# pca63100_current_measurement.net
KiCad netlist of a schematic drawn in Altium Designer
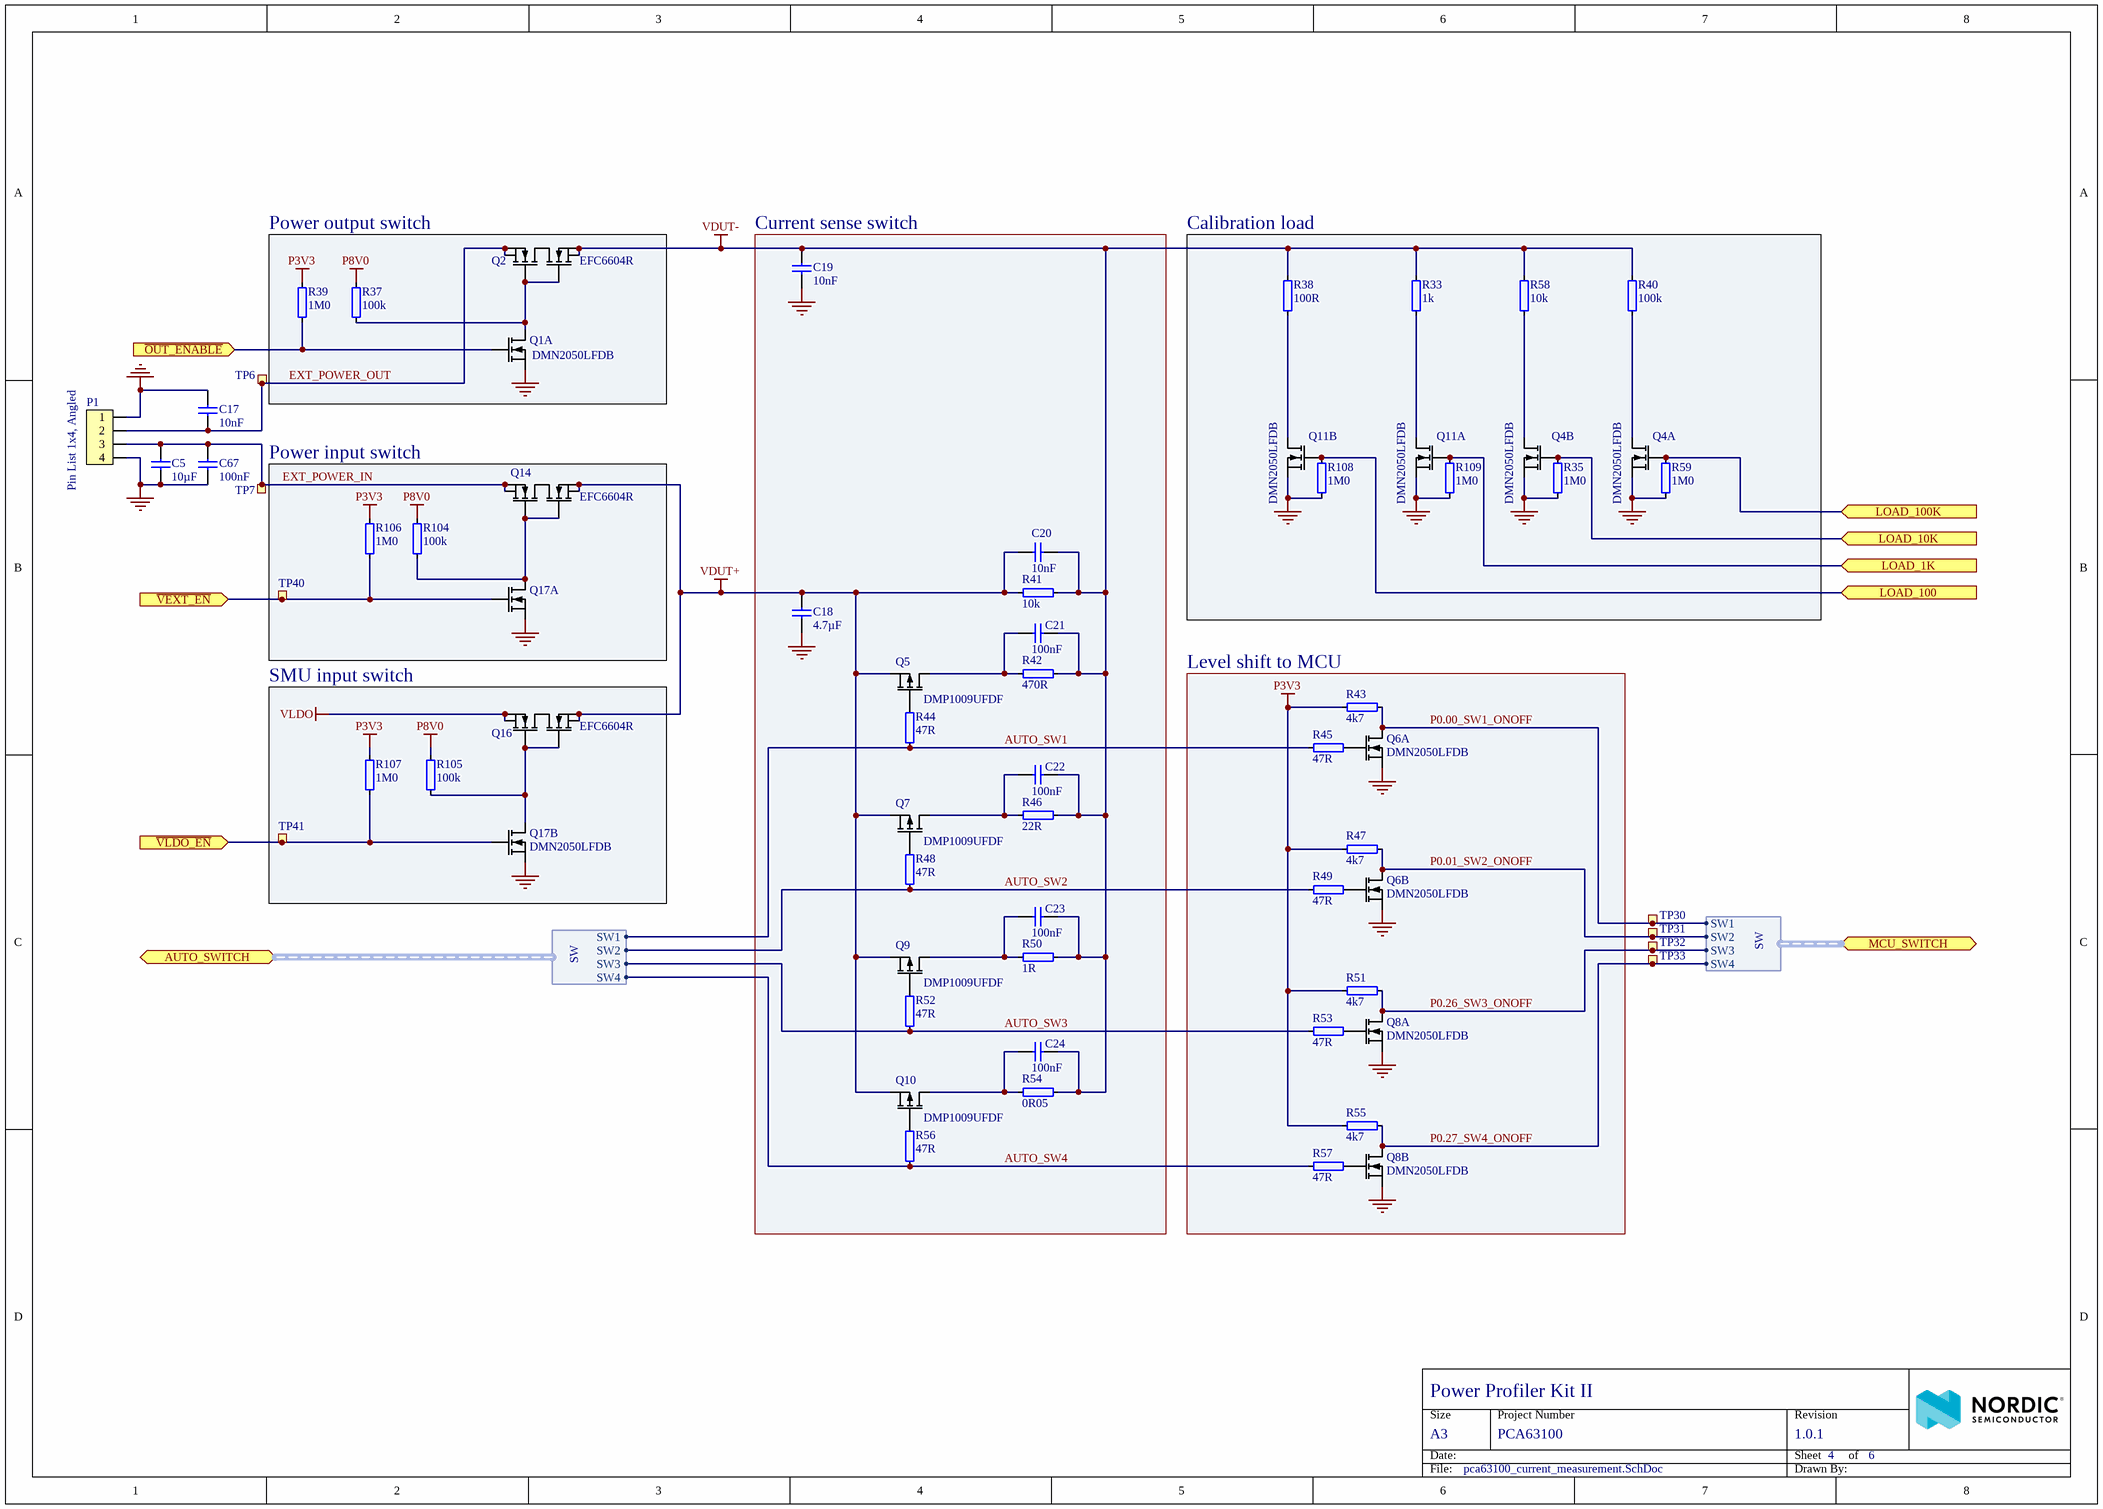
[diagram p0: pca63100_current_measurement.SchDoc]

(export (version "E")
  (design (tool "Eeschema 10.0.6"))
  (components
    (comp (ref "C5")
      (value "10µF")
      (footprint "CAPC1608X06L")
      (description "CAP CER 10UF 10V X7T 0603")
      (fields
        (field (name "PART NUMBER") "0603-10u-10V-X7T-GRM188")
        (field (name "MANUFACTURER") "Murata")
        (field (name "PUBLISHER") "Nordic Semiconductor")
      )
      (libsource (lib "AltiumLib") (part "CAP"))
    )
    (comp (ref "C17")
      (value "10nF")
      (footprint "CAPC0603X03L_C")
      (description "Capacitor, X7R, ±10%")
      (fields (field (name "PART NUMBER") "C0201-10n") (field (name "PUBLISHER") "Nordic Semiconductor"))
      (libsource (lib "AltiumLib") (part "CAP"))
    )
    (comp (ref "C18")
      (value "4.7µF")
      (footprint "CAPC1005X04L")
      (description "Capacitor, X5R, ±20%")
      (fields (field (name "PART NUMBER") "C0402-4µ7") (field (name "PUBLISHER") "Nordic Semiconductor"))
      (libsource (lib "AltiumLib") (part "CAP"))
    )
    (comp (ref "C19")
      (value "10nF")
      (footprint "CAPC0603X03L_C")
      (description "Capacitor, X7R, ±10%")
      (fields (field (name "PART NUMBER") "C0201-10n") (field (name "PUBLISHER") "Nordic Semiconductor"))
      (libsource (lib "AltiumLib") (part "CAP"))
    )
    (comp (ref "C20")
      (value "10nF")
      (footprint "CAPC0603X03L_C")
      (description "Capacitor, X7R, ±10%")
      (fields (field (name "PART NUMBER") "C0201-10n") (field (name "PUBLISHER") "Nordic Semiconductor"))
      (libsource (lib "AltiumLib") (part "CAP"))
    )
    (comp (ref "C21")
      (value "100nF")
      (footprint "CAPC0603X03L_C")
      (description "Capacitor, X5R, ±10%")
      (fields (field (name "PART NUMBER") "C0201-100n") (field (name "PUBLISHER") "Nordic Semiconductor"))
      (libsource (lib "AltiumLib") (part "CAP"))
    )
    (comp (ref "C22")
      (value "100nF")
      (footprint "CAPC0603X03L_C")
      (description "Capacitor, X5R, ±10%")
      (fields (field (name "PART NUMBER") "C0201-100n") (field (name "PUBLISHER") "Nordic Semiconductor"))
      (libsource (lib "AltiumLib") (part "CAP"))
    )
    (comp (ref "C23")
      (value "100nF")
      (footprint "CAPC0603X03L_C")
      (description "Capacitor, X5R, ±10%")
      (fields (field (name "PART NUMBER") "C0201-100n") (field (name "PUBLISHER") "Nordic Semiconductor"))
      (libsource (lib "AltiumLib") (part "CAP"))
    )
    (comp (ref "C24")
      (value "100nF")
      (footprint "CAPC0603X03L_C")
      (description "Capacitor, X5R, ±10%")
      (fields (field (name "PART NUMBER") "C0201-100n") (field (name "PUBLISHER") "Nordic Semiconductor"))
      (libsource (lib "AltiumLib") (part "CAP"))
    )
    (comp (ref "C67")
      (value "100nF")
      (footprint "CAPC0603X03L_C")
      (description "Capacitor, X5R, ±10%")
      (fields (field (name "PART NUMBER") "C0201-100n") (field (name "PUBLISHER") "Nordic Semiconductor"))
      (libsource (lib "AltiumLib") (part "CAP"))
    )
    (comp (ref "P1")
      (value "Pin List 1x4, Angled")
      (footprint "LIST_ANG_1x4-SMD-2.54MM")
      (description "Pin List 1x4, 2.54mm (100mil), Right Angled, SMD")
      (fields
        (field (name "PART NUMBER") "Pin List Ang 1x4 SMD, 2.54mm")
        (field (name "PUBLISHER") "Nordic Semiconductor")
      )
      (libsource (lib "AltiumLib") (part "CONN-4"))
    )
    (comp (ref "Q1")
      (value "DMN2050LFDB")
      (footprint "DFN65P200X60_HS-6N")
      (description "Dual N Ch MOFET, 3.3A, 45mOhm @ 5A, 4.5V, 730mW")
      (fields
        (field (name "MANUFACTURER") "Diodes Incorporated")
        (field (name "MANUFACTURER PART NUMBER") "DMN2050LFDB-7")
        (field (name "PUBLISHER") "Nordic Semiconductor")
      )
      (libsource (lib "AltiumLib") (part "T{colon}FET-N-DUAL"))
    )
    (comp (ref "Q2")
      (value "EFC6604R")
      (footprint "BGA6C65P2X3_146X191X22")
      (description "Dual MOSFET, Dual N Channel, 13 A, 12 V, 0.009 ohm, 4.5 V, 2.5 V")
      (fields
        (field (name "MANUFACTURER") "ON Semiconductor")
        (field (name "MANUFACTURER PART NUMBER") "EFC6604R-TR")
        (field (name "PUBLISHER") "Nordic Semiconductor")
      )
      (libsource (lib "AltiumLib") (part "EFC6604R"))
    )
    (comp (ref "Q4")
      (value "DMN2050LFDB")
      (footprint "DFN65P200X60_HS-6N")
      (description "Dual N Ch MOFET, 3.3A, 45mOhm @ 5A, 4.5V, 730mW")
      (fields
        (field (name "MANUFACTURER") "Diodes Incorporated")
        (field (name "MANUFACTURER PART NUMBER") "DMN2050LFDB-7")
        (field (name "PUBLISHER") "Nordic Semiconductor")
      )
      (libsource (lib "AltiumLib") (part "T{colon}FET-N-DUAL"))
    )
    (comp (ref "Q5")
      (value "DMP1009UFDF")
      (footprint "UDFN65P200X200X60_HS-6N")
      (description "P Ch MOFET, 11A, 30mOhm max, 2W")
      (fields
        (field (name "MANUFACTURER") "Diodes Incorporated")
        (field (name "PUBLISHER") "Nordic Semiconductor")
      )
      (libsource (lib "AltiumLib") (part "T{colon}FET-P"))
    )
    (comp (ref "Q6")
      (value "DMN2050LFDB")
      (footprint "DFN65P200X60_HS-6N")
      (description "Dual N Ch MOFET, 3.3A, 45mOhm @ 5A, 4.5V, 730mW")
      (fields
        (field (name "MANUFACTURER") "Diodes Incorporated")
        (field (name "MANUFACTURER PART NUMBER") "DMN2050LFDB-7")
        (field (name "PUBLISHER") "Nordic Semiconductor")
      )
      (libsource (lib "AltiumLib") (part "T{colon}FET-N-DUAL"))
    )
    (comp (ref "Q7")
      (value "DMP1009UFDF")
      (footprint "UDFN65P200X200X60_HS-6N")
      (description "P Ch MOFET, 11A, 30mOhm max, 2W")
      (fields
        (field (name "MANUFACTURER") "Diodes Incorporated")
        (field (name "PUBLISHER") "Nordic Semiconductor")
      )
      (libsource (lib "AltiumLib") (part "T{colon}FET-P"))
    )
    (comp (ref "Q8")
      (value "DMN2050LFDB")
      (footprint "DFN65P200X60_HS-6N")
      (description "Dual N Ch MOFET, 3.3A, 45mOhm @ 5A, 4.5V, 730mW")
      (fields
        (field (name "MANUFACTURER") "Diodes Incorporated")
        (field (name "MANUFACTURER PART NUMBER") "DMN2050LFDB-7")
        (field (name "PUBLISHER") "Nordic Semiconductor")
      )
      (libsource (lib "AltiumLib") (part "T{colon}FET-N-DUAL"))
    )
    (comp (ref "Q9")
      (value "DMP1009UFDF")
      (footprint "UDFN65P200X200X60_HS-6N")
      (description "P Ch MOFET, 11A, 30mOhm max, 2W")
      (fields
        (field (name "MANUFACTURER") "Diodes Incorporated")
        (field (name "PUBLISHER") "Nordic Semiconductor")
      )
      (libsource (lib "AltiumLib") (part "T{colon}FET-P"))
    )
    (comp (ref "Q10")
      (value "DMP1009UFDF")
      (footprint "UDFN65P200X200X60_HS-6N")
      (description "P Ch MOFET, 11A, 30mOhm max, 2W")
      (fields
        (field (name "MANUFACTURER") "Diodes Incorporated")
        (field (name "PUBLISHER") "Nordic Semiconductor")
      )
      (libsource (lib "AltiumLib") (part "T{colon}FET-P"))
    )
    (comp (ref "Q11")
      (value "DMN2050LFDB")
      (footprint "DFN65P200X60_HS-6N")
      (description "Dual N Ch MOFET, 3.3A, 45mOhm @ 5A, 4.5V, 730mW")
      (fields
        (field (name "MANUFACTURER") "Diodes Incorporated")
        (field (name "MANUFACTURER PART NUMBER") "DMN2050LFDB-7")
        (field (name "PUBLISHER") "Nordic Semiconductor")
      )
      (libsource (lib "AltiumLib") (part "T{colon}FET-N-DUAL"))
    )
    (comp (ref "Q14")
      (value "EFC6604R")
      (footprint "BGA6C65P2X3_146X191X22")
      (description "Dual MOSFET, Dual N Channel, 13 A, 12 V, 0.009 ohm, 4.5 V, 2.5 V")
      (fields
        (field (name "MANUFACTURER") "ON Semiconductor")
        (field (name "MANUFACTURER PART NUMBER") "EFC6604R-TR")
        (field (name "PUBLISHER") "Nordic Semiconductor")
      )
      (libsource (lib "AltiumLib") (part "EFC6604R"))
    )
    (comp (ref "Q16")
      (value "EFC6604R")
      (footprint "BGA6C65P2X3_146X191X22")
      (description "Dual MOSFET, Dual N Channel, 13 A, 12 V, 0.009 ohm, 4.5 V, 2.5 V")
      (fields
        (field (name "MANUFACTURER") "ON Semiconductor")
        (field (name "MANUFACTURER PART NUMBER") "EFC6604R-TR")
        (field (name "PUBLISHER") "Nordic Semiconductor")
      )
      (libsource (lib "AltiumLib") (part "EFC6604R"))
    )
    (comp (ref "Q17")
      (value "DMN2050LFDB")
      (footprint "DFN65P200X60_HS-6N")
      (description "Dual N Ch MOFET, 3.3A, 45mOhm @ 5A, 4.5V, 730mW")
      (fields
        (field (name "MANUFACTURER") "Diodes Incorporated")
        (field (name "MANUFACTURER PART NUMBER") "DMN2050LFDB-7")
        (field (name "PUBLISHER") "Nordic Semiconductor")
      )
      (libsource (lib "AltiumLib") (part "T{colon}FET-N-DUAL"))
    )
    (comp (ref "R33")
      (value "1k")
      (footprint "RESC1005X04L")
      (description "Resistor, ±0.1%, 0.063W")
      (fields (field (name "PART NUMBER") "R0402-1k0_0.1%") (field (name "PUBLISHER") "Nordic Semiconductor"))
      (libsource (lib "AltiumLib") (part "RES"))
    )
    (comp (ref "R35")
      (value "1M0")
      (footprint "RESC0603X03L_C")
      (description "Resistor, ±1%, 0.05W")
      (fields (field (name "PART NUMBER") "R0201-1M0") (field (name "PUBLISHER") "Nordic Semiconductor"))
      (libsource (lib "AltiumLib") (part "RES"))
    )
    (comp (ref "R37")
      (value "100k")
      (footprint "RESC0603X03L_C")
      (description "Resistor, ±1%, 0.05W")
      (fields (field (name "PART NUMBER") "R0201-100k") (field (name "PUBLISHER") "Nordic Semiconductor"))
      (libsource (lib "AltiumLib") (part "RES"))
    )
    (comp (ref "R38")
      (value "100R")
      (footprint "RESC2012X11L")
      (description "Resistor, ±1%, 0.125W")
      (fields (field (name "PART NUMBER") "R0805-100") (field (name "PUBLISHER") "Nordic Semiconductor"))
      (libsource (lib "AltiumLib") (part "RES"))
    )
    (comp (ref "R39")
      (value "1M0")
      (footprint "RESC0603X03L_C")
      (description "Resistor, ±1%, 0.05W")
      (fields (field (name "PART NUMBER") "R0201-1M0") (field (name "PUBLISHER") "Nordic Semiconductor"))
      (libsource (lib "AltiumLib") (part "RES"))
    )
    (comp (ref "R40")
      (value "100k")
      (footprint "RESC1005X04L")
      (description "Resistor, ±0.1%, 0.063W")
      (fields
        (field (name "PART NUMBER") "R0402-100k_0.1%")
        (field (name "PUBLISHER") "Nordic Semiconductor")
      )
      (libsource (lib "AltiumLib") (part "RES"))
    )
    (comp (ref "R41")
      (value "10k")
      (footprint "RESC1005X04L")
      (description "Resistor, ±0.1%, 0.063W")
      (fields (field (name "PART NUMBER") "R0402-1k0_0.1%") (field (name "PUBLISHER") "Nordic Semiconductor"))
      (libsource (lib "AltiumLib") (part "RES"))
    )
    (comp (ref "R42")
      (value "470R")
      (footprint "RESC1005X04L")
      (description "Resistor, ±1%, 0.063W")
      (fields (field (name "PART NUMBER") "R0402-110") (field (name "PUBLISHER") "Nordic Semiconductor"))
      (libsource (lib "AltiumLib") (part "RES"))
    )
    (comp (ref "R43")
      (value "4k7")
      (footprint "RESC0603X03L_C")
      (description "Resistor, ±1%, 0.05W")
      (fields (field (name "PART NUMBER") "R0201-4k7") (field (name "PUBLISHER") "Nordic Semiconductor"))
      (libsource (lib "AltiumLib") (part "RES"))
    )
    (comp (ref "R44")
      (value "47R")
      (footprint "RESC0603X03L_C")
      (description "Resistor, ±1%, 0.05W")
      (fields (field (name "PART NUMBER") "R0201-47R") (field (name "PUBLISHER") "Nordic Semiconductor"))
      (libsource (lib "AltiumLib") (part "RES"))
    )
    (comp (ref "R45")
      (value "47R")
      (footprint "RESC0603X03L_C")
      (description "Resistor, ±1%, 0.05W")
      (fields (field (name "PART NUMBER") "R0201-47R") (field (name "PUBLISHER") "Nordic Semiconductor"))
      (libsource (lib "AltiumLib") (part "RES"))
    )
    (comp (ref "R46")
      (value "22R")
      (footprint "RESC1005X04L")
      (description "Resistor, ±1%, 0.063W")
      (fields (field (name "PART NUMBER") "R0402-11R") (field (name "PUBLISHER") "Nordic Semiconductor"))
      (libsource (lib "AltiumLib") (part "RES"))
    )
    (comp (ref "R47")
      (value "4k7")
      (footprint "RESC0603X03L_C")
      (description "Resistor, ±1%, 0.05W")
      (fields (field (name "PART NUMBER") "R0201-4k7") (field (name "PUBLISHER") "Nordic Semiconductor"))
      (libsource (lib "AltiumLib") (part "RES"))
    )
    (comp (ref "R48")
      (value "47R")
      (footprint "RESC0603X03L_C")
      (description "Resistor, ±1%, 0.05W")
      (fields (field (name "PART NUMBER") "R0201-47R") (field (name "PUBLISHER") "Nordic Semiconductor"))
      (libsource (lib "AltiumLib") (part "RES"))
    )
    (comp (ref "R49")
      (value "47R")
      (footprint "RESC0603X03L_C")
      (description "Resistor, ±1%, 0.05W")
      (fields (field (name "PART NUMBER") "R0201-47R") (field (name "PUBLISHER") "Nordic Semiconductor"))
      (libsource (lib "AltiumLib") (part "RES"))
    )
    (comp (ref "R50")
      (value "1R")
      (footprint "RESC1005X04L")
      (description "Resistor, ±1%, 0.063W")
      (fields (field (name "PART NUMBER") "R0402-1R0") (field (name "PUBLISHER") "Nordic Semiconductor"))
      (libsource (lib "AltiumLib") (part "RES"))
    )
    (comp (ref "R51")
      (value "4k7")
      (footprint "RESC0603X03L_C")
      (description "Resistor, ±1%, 0.05W")
      (fields (field (name "PART NUMBER") "R0201-4k7") (field (name "PUBLISHER") "Nordic Semiconductor"))
      (libsource (lib "AltiumLib") (part "RES"))
    )
    (comp (ref "R52")
      (value "47R")
      (footprint "RESC0603X03L_C")
      (description "Resistor, ±1%, 0.05W")
      (fields (field (name "PART NUMBER") "R0201-47R") (field (name "PUBLISHER") "Nordic Semiconductor"))
      (libsource (lib "AltiumLib") (part "RES"))
    )
    (comp (ref "R53")
      (value "47R")
      (footprint "RESC0603X03L_C")
      (description "Resistor, ±1%, 0.05W")
      (fields (field (name "PART NUMBER") "R0201-47R") (field (name "PUBLISHER") "Nordic Semiconductor"))
      (libsource (lib "AltiumLib") (part "RES"))
    )
    (comp (ref "R54")
      (value "0R05")
      (footprint "RESC1005X04L")
      (description "RES SMD 0.051 OHM 1% 1/4W 0402")
      (fields
        (field (name "PART NUMBER") "R0402-0R051")
        (field (name "MANUFACTURER") "Panasonic")
        (field (name "PUBLISHER") "Nordic Semiconductor")
      )
      (libsource (lib "AltiumLib") (part "RES"))
    )
    (comp (ref "R55")
      (value "4k7")
      (footprint "RESC0603X03L_C")
      (description "Resistor, ±1%, 0.05W")
      (fields (field (name "PART NUMBER") "R0201-4k7") (field (name "PUBLISHER") "Nordic Semiconductor"))
      (libsource (lib "AltiumLib") (part "RES"))
    )
    (comp (ref "R56")
      (value "47R")
      (footprint "RESC0603X03L_C")
      (description "Resistor, ±1%, 0.05W")
      (fields (field (name "PART NUMBER") "R0201-47R") (field (name "PUBLISHER") "Nordic Semiconductor"))
      (libsource (lib "AltiumLib") (part "RES"))
    )
    (comp (ref "R57")
      (value "47R")
      (footprint "RESC0603X03L_C")
      (description "Resistor, ±1%, 0.05W")
      (fields (field (name "PART NUMBER") "R0201-47R") (field (name "PUBLISHER") "Nordic Semiconductor"))
      (libsource (lib "AltiumLib") (part "RES"))
    )
    (comp (ref "R58")
      (value "10k")
      (footprint "RESC0603X03L_C")
      (description "Resistor, ±0.1%, 0.031W")
      (fields (field (name "PART NUMBER") "R0201-10k_0.1%") (field (name "PUBLISHER") "Nordic Semiconductor"))
      (libsource (lib "AltiumLib") (part "RES"))
    )
    (comp (ref "R59")
      (value "1M0")
      (footprint "RESC0603X03L_C")
      (description "Resistor, ±1%, 0.05W")
      (fields (field (name "PART NUMBER") "R0201-1M0") (field (name "PUBLISHER") "Nordic Semiconductor"))
      (libsource (lib "AltiumLib") (part "RES"))
    )
    (comp (ref "R104")
      (value "100k")
      (footprint "RESC0603X03L_C")
      (description "Resistor, ±1%, 0.05W")
      (fields (field (name "PART NUMBER") "R0201-100k") (field (name "PUBLISHER") "Nordic Semiconductor"))
      (libsource (lib "AltiumLib") (part "RES"))
    )
    (comp (ref "R105")
      (value "100k")
      (footprint "RESC0603X03L_C")
      (description "Resistor, ±1%, 0.05W")
      (fields (field (name "PART NUMBER") "R0201-100k") (field (name "PUBLISHER") "Nordic Semiconductor"))
      (libsource (lib "AltiumLib") (part "RES"))
    )
    (comp (ref "R106")
      (value "1M0")
      (footprint "RESC0603X03L_C")
      (description "Resistor, ±1%, 0.05W")
      (fields (field (name "PART NUMBER") "R0201-1M0") (field (name "PUBLISHER") "Nordic Semiconductor"))
      (libsource (lib "AltiumLib") (part "RES"))
    )
    (comp (ref "R107")
      (value "1M0")
      (footprint "RESC0603X03L_C")
      (description "Resistor, ±1%, 0.05W")
      (fields (field (name "PART NUMBER") "R0201-1M0") (field (name "PUBLISHER") "Nordic Semiconductor"))
      (libsource (lib "AltiumLib") (part "RES"))
    )
    (comp (ref "R108")
      (value "1M0")
      (footprint "RESC0603X03L_C")
      (description "Resistor, ±1%, 0.05W")
      (fields (field (name "PART NUMBER") "R0201-1M0") (field (name "PUBLISHER") "Nordic Semiconductor"))
      (libsource (lib "AltiumLib") (part "RES"))
    )
    (comp (ref "R109")
      (value "1M0")
      (footprint "RESC0603X03L_C")
      (description "Resistor, ±1%, 0.05W")
      (fields (field (name "PART NUMBER") "R0201-1M0") (field (name "PUBLISHER") "Nordic Semiconductor"))
      (libsource (lib "AltiumLib") (part "RES"))
    )
    (comp (ref "TP6")
      (value "Ø1.5mm,SMD")
      (footprint "TP_SMD_Ø1.5mm")
      (description "1.5mm circular SMD testpad")
      (fields
        (field (name "PART NUMBER") "TP_SMD_Ø1.5MM")
        (field (name "MANUFACTURER") "Nordic Semiconductor")
        (field (name "PUBLISHER") "Nordic Semiconductor")
      )
      (libsource (lib "AltiumLib") (part "TESTPAD"))
    )
    (comp (ref "TP7")
      (value "Ø1.5mm,SMD")
      (footprint "TP_SMD_Ø1.5mm")
      (description "1.5mm circular SMD testpad")
      (fields
        (field (name "PART NUMBER") "TP_SMD_Ø1.5MM")
        (field (name "MANUFACTURER") "Nordic Semiconductor")
        (field (name "PUBLISHER") "Nordic Semiconductor")
      )
      (libsource (lib "") (part "TESTPAD_1"))
    )
    (comp (ref "TP30")
      (value "Ø0.7mm,SMD")
      (footprint "TP_SMD_Ø0.7mm")
      (description "0.7mm circular SMD testpad")
      (fields
        (field (name "PART NUMBER") "TP_SMD_Ø0.7MM")
        (field (name "MANUFACTURER") "Nordic Semiconductor")
        (field (name "PUBLISHER") "Nordic Semiconductor")
      )
      (libsource (lib "AltiumLib") (part "TESTPAD"))
    )
    (comp (ref "TP31")
      (value "Ø0.7mm,SMD")
      (footprint "TP_SMD_Ø0.7mm")
      (description "0.7mm circular SMD testpad")
      (fields
        (field (name "PART NUMBER") "TP_SMD_Ø0.7MM")
        (field (name "MANUFACTURER") "Nordic Semiconductor")
        (field (name "PUBLISHER") "Nordic Semiconductor")
      )
      (libsource (lib "AltiumLib") (part "TESTPAD"))
    )
    (comp (ref "TP32")
      (value "Ø0.7mm,SMD")
      (footprint "TP_SMD_Ø0.7mm")
      (description "0.7mm circular SMD testpad")
      (fields
        (field (name "PART NUMBER") "TP_SMD_Ø0.7MM")
        (field (name "MANUFACTURER") "Nordic Semiconductor")
        (field (name "PUBLISHER") "Nordic Semiconductor")
      )
      (libsource (lib "AltiumLib") (part "TESTPAD"))
    )
    (comp (ref "TP33")
      (value "Ø0.7mm,SMD")
      (footprint "TP_SMD_Ø0.7mm")
      (description "0.7mm circular SMD testpad")
      (fields
        (field (name "PART NUMBER") "TP_SMD_Ø0.7MM")
        (field (name "MANUFACTURER") "Nordic Semiconductor")
        (field (name "PUBLISHER") "Nordic Semiconductor")
      )
      (libsource (lib "AltiumLib") (part "TESTPAD"))
    )
    (comp (ref "TP40")
      (value "Ø0.7mm,SMD")
      (footprint "TP_SMD_Ø0.7mm")
      (description "0.7mm circular SMD testpad")
      (fields
        (field (name "PART NUMBER") "TP_SMD_Ø0.7MM")
        (field (name "MANUFACTURER") "Nordic Semiconductor")
        (field (name "PUBLISHER") "Nordic Semiconductor")
      )
      (libsource (lib "AltiumLib") (part "TESTPAD"))
    )
    (comp (ref "TP41")
      (value "Ø0.7mm,SMD")
      (footprint "TP_SMD_Ø0.7mm")
      (description "0.7mm circular SMD testpad")
      (fields
        (field (name "PART NUMBER") "TP_SMD_Ø0.7MM")
        (field (name "MANUFACTURER") "Nordic Semiconductor")
        (field (name "PUBLISHER") "Nordic Semiconductor")
      )
      (libsource (lib "AltiumLib") (part "TESTPAD"))
    )
  )
  (nets
    (net (code "2") (name "/AUTO_SW1") (class "Default")
      (node (ref "R44") (pin "1") (pinfunction "1_1") (pintype "passive"))
      (node (ref "R45") (pin "2") (pinfunction "2_2") (pintype "passive"))
    )
    (net (code "3") (name "/AUTO_SW2") (class "Default")
      (node (ref "R48") (pin "1") (pinfunction "1_1") (pintype "passive"))
      (node (ref "R49") (pin "2") (pinfunction "2_2") (pintype "passive"))
    )
    (net (code "4") (name "/AUTO_SW3") (class "Default")
      (node (ref "R52") (pin "1") (pinfunction "1_1") (pintype "passive"))
      (node (ref "R53") (pin "2") (pinfunction "2_2") (pintype "passive"))
    )
    (net (code "5") (name "/AUTO_SW4") (class "Default")
      (node (ref "R56") (pin "1") (pinfunction "1_1") (pintype "passive"))
      (node (ref "R57") (pin "2") (pinfunction "2_2") (pintype "passive"))
    )
    (net (code "6") (name "/EXT_POWER_IN") (class "Default")
      (node (ref "C5") (pin "1") (pinfunction "1_1") (pintype "passive"))
      (node (ref "C67") (pin "1") (pinfunction "1_1") (pintype "passive"))
      (node (ref "P1") (pin "3") (pinfunction "3_3") (pintype "passive"))
      (node (ref "Q14") (pin "4") (pinfunction "S2_4") (pintype "passive"))
      (node (ref "Q14") (pin "6") (pinfunction "S2_6") (pintype "passive"))
      (node (ref "TP7") (pin "1") (pinfunction "1_1") (pintype "passive"))
    )
    (net (code "7") (name "/EXT_POWER_OUT") (class "Default")
      (node (ref "C17") (pin "2") (pinfunction "2_2") (pintype "passive"))
      (node (ref "P1") (pin "2") (pinfunction "2_2") (pintype "passive"))
      (node (ref "Q2") (pin "4") (pinfunction "S2_4") (pintype "passive"))
      (node (ref "Q2") (pin "6") (pinfunction "S2_6") (pintype "passive"))
      (node (ref "TP6") (pin "1") (pinfunction "1_1") (pintype "passive"))
    )
    (net (code "8") (name "/LOAD_1K") (class "Default")
      (node (ref "Q11") (pin "2") (pinfunction "G1_2") (pintype "passive"))
      (node (ref "R109") (pin "2") (pinfunction "2_2") (pintype "passive"))
    )
    (net (code "9") (name "/LOAD_10K") (class "Default")
      (node (ref "Q4") (pin "5") (pinfunction "G2_5") (pintype "passive"))
      (node (ref "R35") (pin "2") (pinfunction "2_2") (pintype "passive"))
    )
    (net (code "10") (name "/LOAD_100") (class "Default")
      (node (ref "Q11") (pin "5") (pinfunction "G2_5") (pintype "passive"))
      (node (ref "R108") (pin "2") (pinfunction "2_2") (pintype "passive"))
    )
    (net (code "11") (name "/LOAD_100K") (class "Default")
      (node (ref "Q4") (pin "2") (pinfunction "G1_2") (pintype "passive"))
      (node (ref "R59") (pin "2") (pinfunction "2_2") (pintype "passive"))
    )
    (net (code "12") (name "/P0.00_SW1_ONOFF") (class "Default")
      (node (ref "Q6") (pin "6") (pinfunction "D1_6") (pintype "passive"))
      (node (ref "R43") (pin "1") (pinfunction "1_1") (pintype "passive"))
      (node (ref "TP30") (pin "1") (pinfunction "1_1") (pintype "passive"))
    )
    (net (code "13") (name "/P0.01_SW2_ONOFF") (class "Default")
      (node (ref "Q6") (pin "3") (pinfunction "D2_3") (pintype "passive"))
      (node (ref "R47") (pin "1") (pinfunction "1_1") (pintype "passive"))
      (node (ref "TP31") (pin "1") (pinfunction "1_1") (pintype "passive"))
    )
    (net (code "14") (name "/P0.26_SW3_ONOFF") (class "Default")
      (node (ref "Q8") (pin "6") (pinfunction "D1_6") (pintype "passive"))
      (node (ref "R51") (pin "1") (pinfunction "1_1") (pintype "passive"))
      (node (ref "TP32") (pin "1") (pinfunction "1_1") (pintype "passive"))
    )
    (net (code "15") (name "/P0.27_SW4_ONOFF") (class "Default")
      (node (ref "Q8") (pin "3") (pinfunction "D2_3") (pintype "passive"))
      (node (ref "R55") (pin "1") (pinfunction "1_1") (pintype "passive"))
      (node (ref "TP33") (pin "1") (pinfunction "1_1") (pintype "passive"))
    )
    (net (code "17") (name "/~{OUT_ENABLE}") (class "Default")
      (node (ref "Q1") (pin "2") (pinfunction "G1_2") (pintype "passive"))
      (node (ref "R39") (pin "1") (pinfunction "1_1") (pintype "passive"))
    )
    (net (code "18") (name "/~{VEXT_EN}") (class "Default")
      (node (ref "Q17") (pin "2") (pinfunction "G1_2") (pintype "passive"))
      (node (ref "R106") (pin "1") (pinfunction "1_1") (pintype "passive"))
      (node (ref "TP40") (pin "1") (pinfunction "1_1") (pintype "passive"))
    )
    (net (code "19") (name "/~{VLDO_EN}") (class "Default")
      (node (ref "Q17") (pin "5") (pinfunction "G2_5") (pintype "passive"))
      (node (ref "R107") (pin "1") (pinfunction "1_1") (pintype "passive"))
      (node (ref "TP41") (pin "1") (pinfunction "1_1") (pintype "passive"))
    )
    (net (code "20") (name "GND") (class "Default")
      (node (ref "C17") (pin "1") (pinfunction "1_1") (pintype "passive"))
      (node (ref "C18") (pin "2") (pinfunction "2_2") (pintype "passive"))
      (node (ref "C19") (pin "1") (pinfunction "1_1") (pintype "passive"))
      (node (ref "C5") (pin "2") (pinfunction "2_2") (pintype "passive"))
      (node (ref "C67") (pin "2") (pinfunction "2_2") (pintype "passive"))
      (node (ref "P1") (pin "1") (pinfunction "1_1") (pintype "passive"))
      (node (ref "P1") (pin "4") (pinfunction "4_4") (pintype "passive"))
      (node (ref "Q1") (pin "1") (pinfunction "S1_1") (pintype "passive"))
      (node (ref "Q11") (pin "1") (pinfunction "S1_1") (pintype "passive"))
      (node (ref "Q11") (pin "4") (pinfunction "S2_4") (pintype "passive"))
      (node (ref "Q17") (pin "1") (pinfunction "S1_1") (pintype "passive"))
      (node (ref "Q17") (pin "4") (pinfunction "S2_4") (pintype "passive"))
      (node (ref "Q4") (pin "1") (pinfunction "S1_1") (pintype "passive"))
      (node (ref "Q4") (pin "4") (pinfunction "S2_4") (pintype "passive"))
      (node (ref "Q6") (pin "1") (pinfunction "S1_1") (pintype "passive"))
      (node (ref "Q6") (pin "4") (pinfunction "S2_4") (pintype "passive"))
      (node (ref "Q8") (pin "1") (pinfunction "S1_1") (pintype "passive"))
      (node (ref "Q8") (pin "4") (pinfunction "S2_4") (pintype "passive"))
      (node (ref "R108") (pin "1") (pinfunction "1_1") (pintype "passive"))
      (node (ref "R109") (pin "1") (pinfunction "1_1") (pintype "passive"))
      (node (ref "R35") (pin "1") (pinfunction "1_1") (pintype "passive"))
      (node (ref "R59") (pin "1") (pinfunction "1_1") (pintype "passive"))
    )
    (net (code "21") (name "Net-(Q1A-D1)") (class "Default")
      (node (ref "Q1") (pin "6") (pinfunction "D1_6") (pintype "passive"))
      (node (ref "Q2") (pin "2") (pinfunction "G1_2") (pintype "passive"))
      (node (ref "Q2") (pin "5") (pinfunction "G2_5") (pintype "passive"))
      (node (ref "R37") (pin "2") (pinfunction "2_2") (pintype "passive"))
    )
    (net (code "22") (name "Net-(Q4A-D1)") (class "Default")
      (node (ref "Q4") (pin "6") (pinfunction "D1_6") (pintype "passive"))
      (node (ref "R40") (pin "1") (pinfunction "1_1") (pintype "passive"))
    )
    (net (code "23") (name "Net-(Q4B-D2)") (class "Default")
      (node (ref "Q4") (pin "3") (pinfunction "D2_3") (pintype "passive"))
      (node (ref "R58") (pin "2") (pinfunction "2_2") (pintype "passive"))
    )
    (net (code "24") (name "Net-(Q5-D)") (class "Default")
      (node (ref "C21") (pin "1") (pinfunction "1_1") (pintype "passive"))
      (node (ref "Q5") (pin "3") (pinfunction "D_3") (pintype "passive"))
      (node (ref "R42") (pin "1") (pinfunction "1_1") (pintype "passive"))
    )
    (net (code "25") (name "Net-(Q5-G)") (class "Default")
      (node (ref "Q5") (pin "1") (pinfunction "G_1") (pintype "passive"))
      (node (ref "R44") (pin "2") (pinfunction "2_2") (pintype "passive"))
    )
    (net (code "26") (name "Net-(Q6A-G1)") (class "Default")
      (node (ref "Q6") (pin "2") (pinfunction "G1_2") (pintype "passive"))
      (node (ref "R45") (pin "1") (pinfunction "1_1") (pintype "passive"))
    )
    (net (code "27") (name "Net-(Q6B-G2)") (class "Default")
      (node (ref "Q6") (pin "5") (pinfunction "G2_5") (pintype "passive"))
      (node (ref "R49") (pin "1") (pinfunction "1_1") (pintype "passive"))
    )
    (net (code "28") (name "Net-(Q7-D)") (class "Default")
      (node (ref "C22") (pin "1") (pinfunction "1_1") (pintype "passive"))
      (node (ref "Q7") (pin "3") (pinfunction "D_3") (pintype "passive"))
      (node (ref "R46") (pin "1") (pinfunction "1_1") (pintype "passive"))
    )
    (net (code "29") (name "Net-(Q7-G)") (class "Default")
      (node (ref "Q7") (pin "1") (pinfunction "G_1") (pintype "passive"))
      (node (ref "R48") (pin "2") (pinfunction "2_2") (pintype "passive"))
    )
    (net (code "30") (name "Net-(Q8A-G1)") (class "Default")
      (node (ref "Q8") (pin "2") (pinfunction "G1_2") (pintype "passive"))
      (node (ref "R53") (pin "1") (pinfunction "1_1") (pintype "passive"))
    )
    (net (code "31") (name "Net-(Q8B-G2)") (class "Default")
      (node (ref "Q8") (pin "5") (pinfunction "G2_5") (pintype "passive"))
      (node (ref "R57") (pin "1") (pinfunction "1_1") (pintype "passive"))
    )
    (net (code "32") (name "Net-(Q9-D)") (class "Default")
      (node (ref "C23") (pin "1") (pinfunction "1_1") (pintype "passive"))
      (node (ref "Q9") (pin "3") (pinfunction "D_3") (pintype "passive"))
      (node (ref "R50") (pin "1") (pinfunction "1_1") (pintype "passive"))
    )
    (net (code "33") (name "Net-(Q9-G)") (class "Default")
      (node (ref "Q9") (pin "1") (pinfunction "G_1") (pintype "passive"))
      (node (ref "R52") (pin "2") (pinfunction "2_2") (pintype "passive"))
    )
    (net (code "34") (name "Net-(Q10-D)") (class "Default")
      (node (ref "C24") (pin "1") (pinfunction "1_1") (pintype "passive"))
      (node (ref "Q10") (pin "3") (pinfunction "D_3") (pintype "passive"))
      (node (ref "R54") (pin "2") (pinfunction "2_2") (pintype "passive"))
    )
    (net (code "35") (name "Net-(Q10-G)") (class "Default")
      (node (ref "Q10") (pin "1") (pinfunction "G_1") (pintype "passive"))
      (node (ref "R56") (pin "2") (pinfunction "2_2") (pintype "passive"))
    )
    (net (code "36") (name "Net-(Q11A-D1)") (class "Default")
      (node (ref "Q11") (pin "6") (pinfunction "D1_6") (pintype "passive"))
      (node (ref "R33") (pin "2") (pinfunction "2_2") (pintype "passive"))
    )
    (net (code "37") (name "Net-(Q11B-D2)") (class "Default")
      (node (ref "Q11") (pin "3") (pinfunction "D2_3") (pintype "passive"))
      (node (ref "R38") (pin "1") (pinfunction "1_1") (pintype "passive"))
    )
    (net (code "38") (name "Net-(Q14-G1)") (class "Default")
      (node (ref "Q14") (pin "2") (pinfunction "G1_2") (pintype "passive"))
      (node (ref "Q14") (pin "5") (pinfunction "G2_5") (pintype "passive"))
      (node (ref "Q17") (pin "6") (pinfunction "D1_6") (pintype "passive"))
      (node (ref "R104") (pin "1") (pinfunction "1_1") (pintype "passive"))
    )
    (net (code "39") (name "Net-(Q16-G1)") (class "Default")
      (node (ref "Q16") (pin "2") (pinfunction "G1_2") (pintype "passive"))
      (node (ref "Q16") (pin "5") (pinfunction "G2_5") (pintype "passive"))
      (node (ref "Q17") (pin "3") (pinfunction "D2_3") (pintype "passive"))
      (node (ref "R105") (pin "1") (pinfunction "1_1") (pintype "passive"))
    )
    (net (code "40") (name "P3V3") (class "Default")
      (node (ref "R106") (pin "2") (pinfunction "2_2") (pintype "passive"))
      (node (ref "R107") (pin "2") (pinfunction "2_2") (pintype "passive"))
      (node (ref "R39") (pin "2") (pinfunction "2_2") (pintype "passive"))
      (node (ref "R43") (pin "2") (pinfunction "2_2") (pintype "passive"))
      (node (ref "R47") (pin "2") (pinfunction "2_2") (pintype "passive"))
      (node (ref "R51") (pin "2") (pinfunction "2_2") (pintype "passive"))
      (node (ref "R55") (pin "2") (pinfunction "2_2") (pintype "passive"))
    )
    (net (code "41") (name "P8V0") (class "Default")
      (node (ref "R104") (pin "2") (pinfunction "2_2") (pintype "passive"))
      (node (ref "R105") (pin "2") (pinfunction "2_2") (pintype "passive"))
      (node (ref "R37") (pin "1") (pinfunction "1_1") (pintype "passive"))
    )
    (net (code "42") (name "VDUT+") (class "Default")
      (node (ref "C18") (pin "1") (pinfunction "1_1") (pintype "passive"))
      (node (ref "C20") (pin "1") (pinfunction "1_1") (pintype "passive"))
      (node (ref "Q10") (pin "2") (pinfunction "S_2") (pintype "passive"))
      (node (ref "Q14") (pin "1") (pinfunction "S1_1") (pintype "passive"))
      (node (ref "Q14") (pin "3") (pinfunction "S2_3") (pintype "passive"))
      (node (ref "Q16") (pin "1") (pinfunction "S1_1") (pintype "passive"))
      (node (ref "Q16") (pin "3") (pinfunction "S2_3") (pintype "passive"))
      (node (ref "Q5") (pin "2") (pinfunction "S_2") (pintype "passive"))
      (node (ref "Q7") (pin "2") (pinfunction "S_2") (pintype "passive"))
      (node (ref "Q9") (pin "2") (pinfunction "S_2") (pintype "passive"))
      (node (ref "R41") (pin "1") (pinfunction "1_1") (pintype "passive"))
    )
    (net (code "43") (name "VDUT-") (class "Default")
      (node (ref "C19") (pin "2") (pinfunction "2_2") (pintype "passive"))
      (node (ref "C20") (pin "2") (pinfunction "2_2") (pintype "passive"))
      (node (ref "C21") (pin "2") (pinfunction "2_2") (pintype "passive"))
      (node (ref "C22") (pin "2") (pinfunction "2_2") (pintype "passive"))
      (node (ref "C23") (pin "2") (pinfunction "2_2") (pintype "passive"))
      (node (ref "C24") (pin "2") (pinfunction "2_2") (pintype "passive"))
      (node (ref "Q2") (pin "1") (pinfunction "S1_1") (pintype "passive"))
      (node (ref "Q2") (pin "3") (pinfunction "S2_3") (pintype "passive"))
      (node (ref "R33") (pin "1") (pinfunction "1_1") (pintype "passive"))
      (node (ref "R38") (pin "2") (pinfunction "2_2") (pintype "passive"))
      (node (ref "R40") (pin "2") (pinfunction "2_2") (pintype "passive"))
      (node (ref "R41") (pin "2") (pinfunction "2_2") (pintype "passive"))
      (node (ref "R42") (pin "2") (pinfunction "2_2") (pintype "passive"))
      (node (ref "R46") (pin "2") (pinfunction "2_2") (pintype "passive"))
      (node (ref "R50") (pin "2") (pinfunction "2_2") (pintype "passive"))
      (node (ref "R54") (pin "1") (pinfunction "1_1") (pintype "passive"))
      (node (ref "R58") (pin "1") (pinfunction "1_1") (pintype "passive"))
    )
    (net (code "44") (name "VLDO") (class "Default")
      (node (ref "Q16") (pin "4") (pinfunction "S2_4") (pintype "passive"))
      (node (ref "Q16") (pin "6") (pinfunction "S2_6") (pintype "passive"))
    )
  )
)
